# 02_BANDPASS.net
KiCad netlist of a schematic drawn in Altium Designer
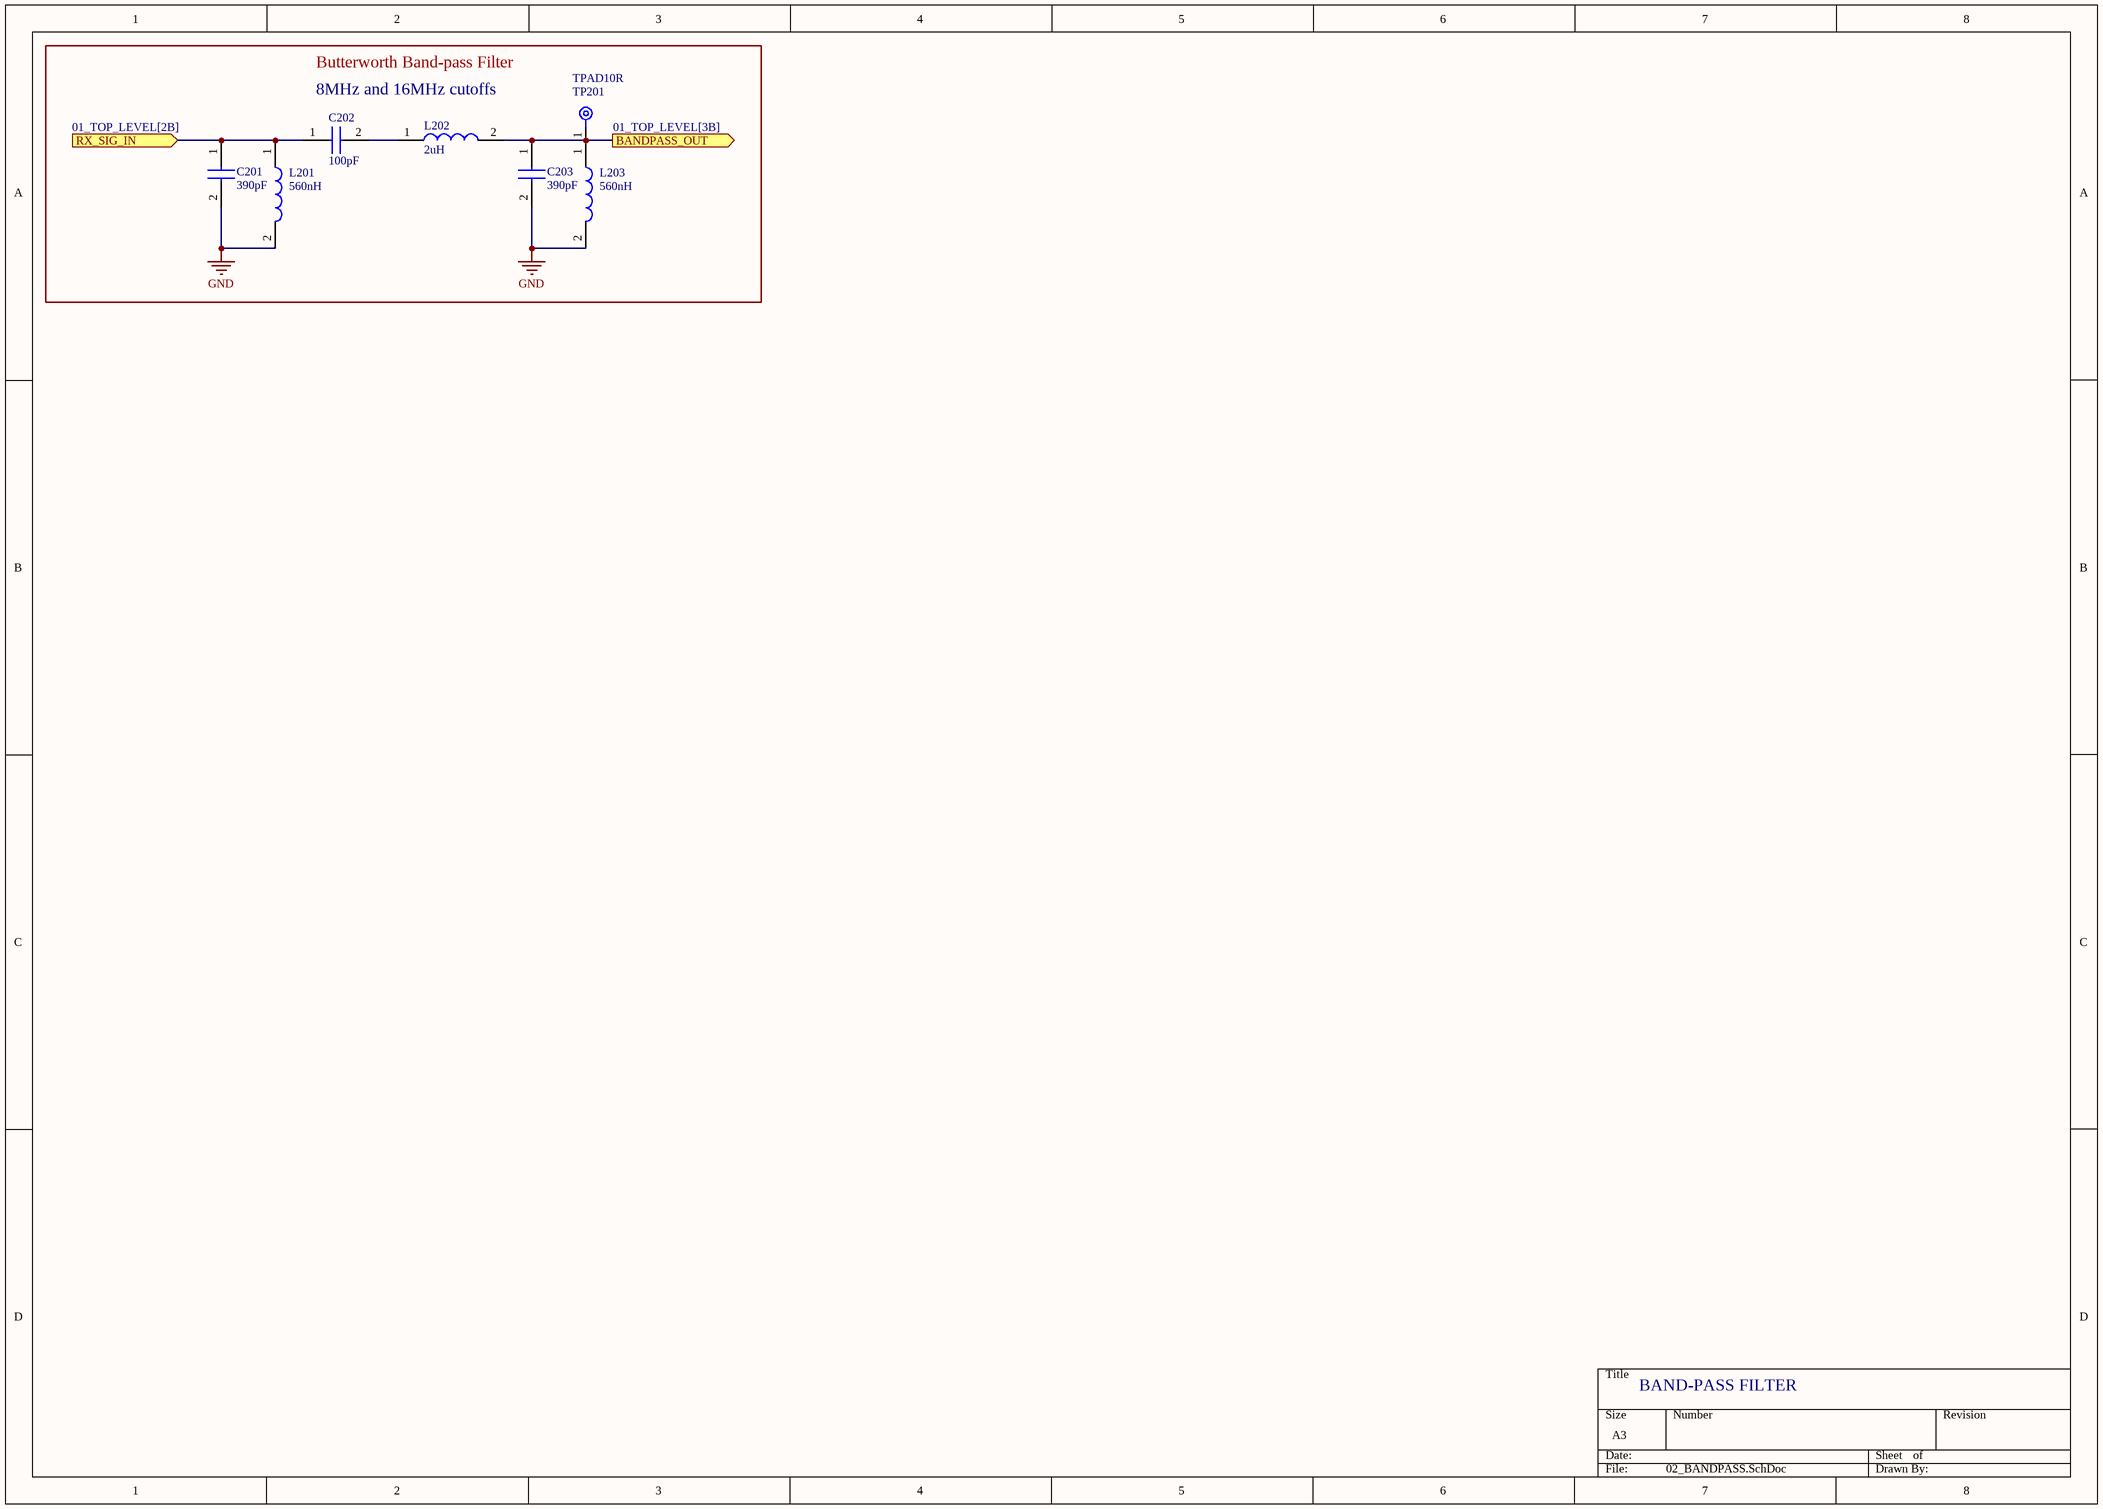
[diagram p0: 02_BANDPASS.SchDoc]

(export (version "E")
  (design (tool "Eeschema 10.0.6"))
  (components
    (comp (ref "C201")
      (value "390pF")
      (footprint "CAP_0805")
      (description "Capacitor SMD 0805")
      (libsource (lib "Passive_Components") (part "CAP_0805"))
    )
    (comp (ref "C202")
      (value "100pF")
      (footprint "CAP_0805")
      (description "Capacitor SMD 0805")
      (libsource (lib "Passive_Components") (part "CAP_0805"))
    )
    (comp (ref "C203")
      (value "390pF")
      (footprint "CAP_0805")
      (description "Capacitor SMD 0805")
      (libsource (lib "Passive_Components") (part "CAP_0805"))
    )
    (comp (ref "L201")
      (value "560nH")
      (footprint "IND_0805")
      (description "Inductor SMD 0805")
      (fields
        (field (name "MANUFACTURER_PART_NUMBER") "74479775147")
        (field (name "MOUSER PART NUMBER") "710-74479775147")
      )
      (libsource (lib "Passive_Components") (part "IND_0805"))
    )
    (comp (ref "L202")
      (value "2uH")
      (footprint "IND_0805")
      (description "Inductor SMD 0805")
      (fields
        (field (name "MANUFACTURER_PART_NUMBER") "74479775147")
        (field (name "MOUSER PART NUMBER") "710-74479775147")
      )
      (libsource (lib "Passive_Components") (part "IND_0805"))
    )
    (comp (ref "L203")
      (value "560nH")
      (footprint "IND_0805")
      (description "Inductor SMD 0805")
      (fields
        (field (name "MANUFACTURER_PART_NUMBER") "74479775147")
        (field (name "MOUSER PART NUMBER") "710-74479775147")
      )
      (libsource (lib "Passive_Components") (part "IND_0805"))
    )
    (comp (ref "TP201")
      (value "TPAD10R")
      (footprint "TEST_POINT")
      (description "Testpont Pad 10R")
      (libsource (lib "PASSIVE_COMPONENTS") (part "TEST_POINT"))
    )
  )
  (nets
    (net (code "1") (name "/BANDPASS_OUT") (class "Default")
      (node (ref "C203") (pin "1") (pinfunction "1_1") (pintype "passive"))
      (node (ref "L202") (pin "2") (pinfunction "2_2") (pintype "passive"))
      (node (ref "L203") (pin "1") (pinfunction "1_1") (pintype "passive"))
      (node (ref "TP201") (pin "1") (pinfunction "1_1") (pintype "passive"))
    )
    (net (code "2") (name "/RX_SIG_IN") (class "Default")
      (node (ref "C201") (pin "1") (pinfunction "1_1") (pintype "passive"))
      (node (ref "C202") (pin "1") (pinfunction "1_1") (pintype "passive"))
      (node (ref "L201") (pin "1") (pinfunction "1_1") (pintype "passive"))
    )
    (net (code "3") (name "GND") (class "Default")
      (node (ref "C201") (pin "2") (pinfunction "2_2") (pintype "passive"))
      (node (ref "C203") (pin "2") (pinfunction "2_2") (pintype "passive"))
      (node (ref "L201") (pin "2") (pinfunction "2_2") (pintype "passive"))
      (node (ref "L203") (pin "2") (pinfunction "2_2") (pintype "passive"))
    )
    (net (code "4") (name "Net-(C202-Pad2)") (class "Default")
      (node (ref "C202") (pin "2") (pinfunction "2_2") (pintype "passive"))
      (node (ref "L202") (pin "1") (pinfunction "1_1") (pintype "passive"))
    )
  )
)
